# digital.net
KiCad netlist of a schematic drawn in Altium Designer
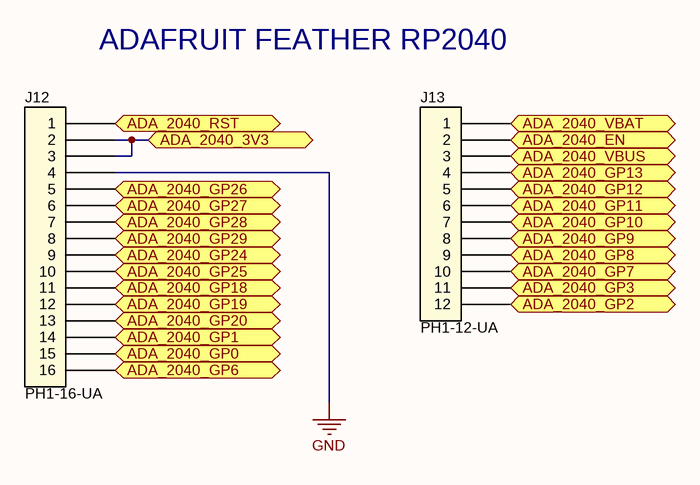
[diagram p0: digital.SchDoc]

(export (version "E")
  (design (tool "Eeschema 10.0.6"))
  (components
    (comp (ref "J12")
      (value "PH1-16-UA")
      (footprint "CONN_ADAM_TECH_PH1-16-UA")
      (description "CONN HEADER VERT 16POS 2.54MM GOLD")
      (fields (field (name "MFR") "Adam Tech"))
      (libsource (lib "General_Library") (part "CMP-007-0080"))
    )
    (comp (ref "J13")
      (value "PH1-12-UA")
      (footprint "CONN_ADAM_TECH_PH1-12-UA")
      (description "CONN HEADER VERT 12POS 2.54MM GOLD")
      (fields (field (name "MFR") "Adam Tech"))
      (libsource (lib "General_Library") (part "CMP-007-0079"))
    )
  )
  (nets
    (net (code "1") (name "/ADA_2040_3V3") (class "Default")
      (node (ref "J12") (pin "2") (pinfunction "2_2") (pintype "passive"))
      (node (ref "J12") (pin "3") (pinfunction "3_3") (pintype "passive"))
    )
    (net (code "2") (name "/ADA_2040_EN") (class "Default")
      (node (ref "J13") (pin "2") (pinfunction "2_2") (pintype "passive"))
    )
    (net (code "3") (name "/ADA_2040_GP0") (class "Default")
      (node (ref "J12") (pin "15") (pinfunction "15_15") (pintype "passive"))
    )
    (net (code "4") (name "/ADA_2040_GP1") (class "Default")
      (node (ref "J12") (pin "14") (pinfunction "14_14") (pintype "passive"))
    )
    (net (code "5") (name "/ADA_2040_GP2") (class "Default")
      (node (ref "J13") (pin "12") (pinfunction "12_12") (pintype "passive"))
    )
    (net (code "6") (name "/ADA_2040_GP3") (class "Default")
      (node (ref "J13") (pin "11") (pinfunction "11_11") (pintype "passive"))
    )
    (net (code "7") (name "/ADA_2040_GP6") (class "Default")
      (node (ref "J12") (pin "16") (pinfunction "16_16") (pintype "passive"))
    )
    (net (code "8") (name "/ADA_2040_GP7") (class "Default")
      (node (ref "J13") (pin "10") (pinfunction "10_10") (pintype "passive"))
    )
    (net (code "9") (name "/ADA_2040_GP8") (class "Default")
      (node (ref "J13") (pin "9") (pinfunction "9_9") (pintype "passive"))
    )
    (net (code "10") (name "/ADA_2040_GP9") (class "Default")
      (node (ref "J13") (pin "8") (pinfunction "8_8") (pintype "passive"))
    )
    (net (code "11") (name "/ADA_2040_GP10") (class "Default")
      (node (ref "J13") (pin "7") (pinfunction "7_7") (pintype "passive"))
    )
    (net (code "12") (name "/ADA_2040_GP11") (class "Default")
      (node (ref "J13") (pin "6") (pinfunction "6_6") (pintype "passive"))
    )
    (net (code "13") (name "/ADA_2040_GP12") (class "Default")
      (node (ref "J13") (pin "5") (pinfunction "5_5") (pintype "passive"))
    )
    (net (code "14") (name "/ADA_2040_GP13") (class "Default")
      (node (ref "J13") (pin "4") (pinfunction "4_4") (pintype "passive"))
    )
    (net (code "15") (name "/ADA_2040_GP18") (class "Default")
      (node (ref "J12") (pin "11") (pinfunction "11_11") (pintype "passive"))
    )
    (net (code "16") (name "/ADA_2040_GP19") (class "Default")
      (node (ref "J12") (pin "12") (pinfunction "12_12") (pintype "passive"))
    )
    (net (code "17") (name "/ADA_2040_GP20") (class "Default")
      (node (ref "J12") (pin "13") (pinfunction "13_13") (pintype "passive"))
    )
    (net (code "18") (name "/ADA_2040_GP24") (class "Default")
      (node (ref "J12") (pin "9") (pinfunction "9_9") (pintype "passive"))
    )
    (net (code "19") (name "/ADA_2040_GP25") (class "Default")
      (node (ref "J12") (pin "10") (pinfunction "10_10") (pintype "passive"))
    )
    (net (code "20") (name "/ADA_2040_GP26") (class "Default")
      (node (ref "J12") (pin "5") (pinfunction "5_5") (pintype "passive"))
    )
    (net (code "21") (name "/ADA_2040_GP27") (class "Default")
      (node (ref "J12") (pin "6") (pinfunction "6_6") (pintype "passive"))
    )
    (net (code "22") (name "/ADA_2040_GP28") (class "Default")
      (node (ref "J12") (pin "7") (pinfunction "7_7") (pintype "passive"))
    )
    (net (code "23") (name "/ADA_2040_GP29") (class "Default")
      (node (ref "J12") (pin "8") (pinfunction "8_8") (pintype "passive"))
    )
    (net (code "24") (name "/ADA_2040_RST") (class "Default")
      (node (ref "J12") (pin "1") (pinfunction "1_1") (pintype "passive"))
    )
    (net (code "25") (name "/ADA_2040_VBAT") (class "Default")
      (node (ref "J13") (pin "1") (pinfunction "1_1") (pintype "passive"))
    )
    (net (code "26") (name "/ADA_2040_VBUS") (class "Default")
      (node (ref "J13") (pin "3") (pinfunction "3_3") (pintype "passive"))
    )
    (net (code "27") (name "GND") (class "Default")
      (node (ref "J12") (pin "4") (pinfunction "4_4") (pintype "passive"))
    )
  )
)
